# durtest4.net
KiCad netlist of a schematic drawn in EAGLE
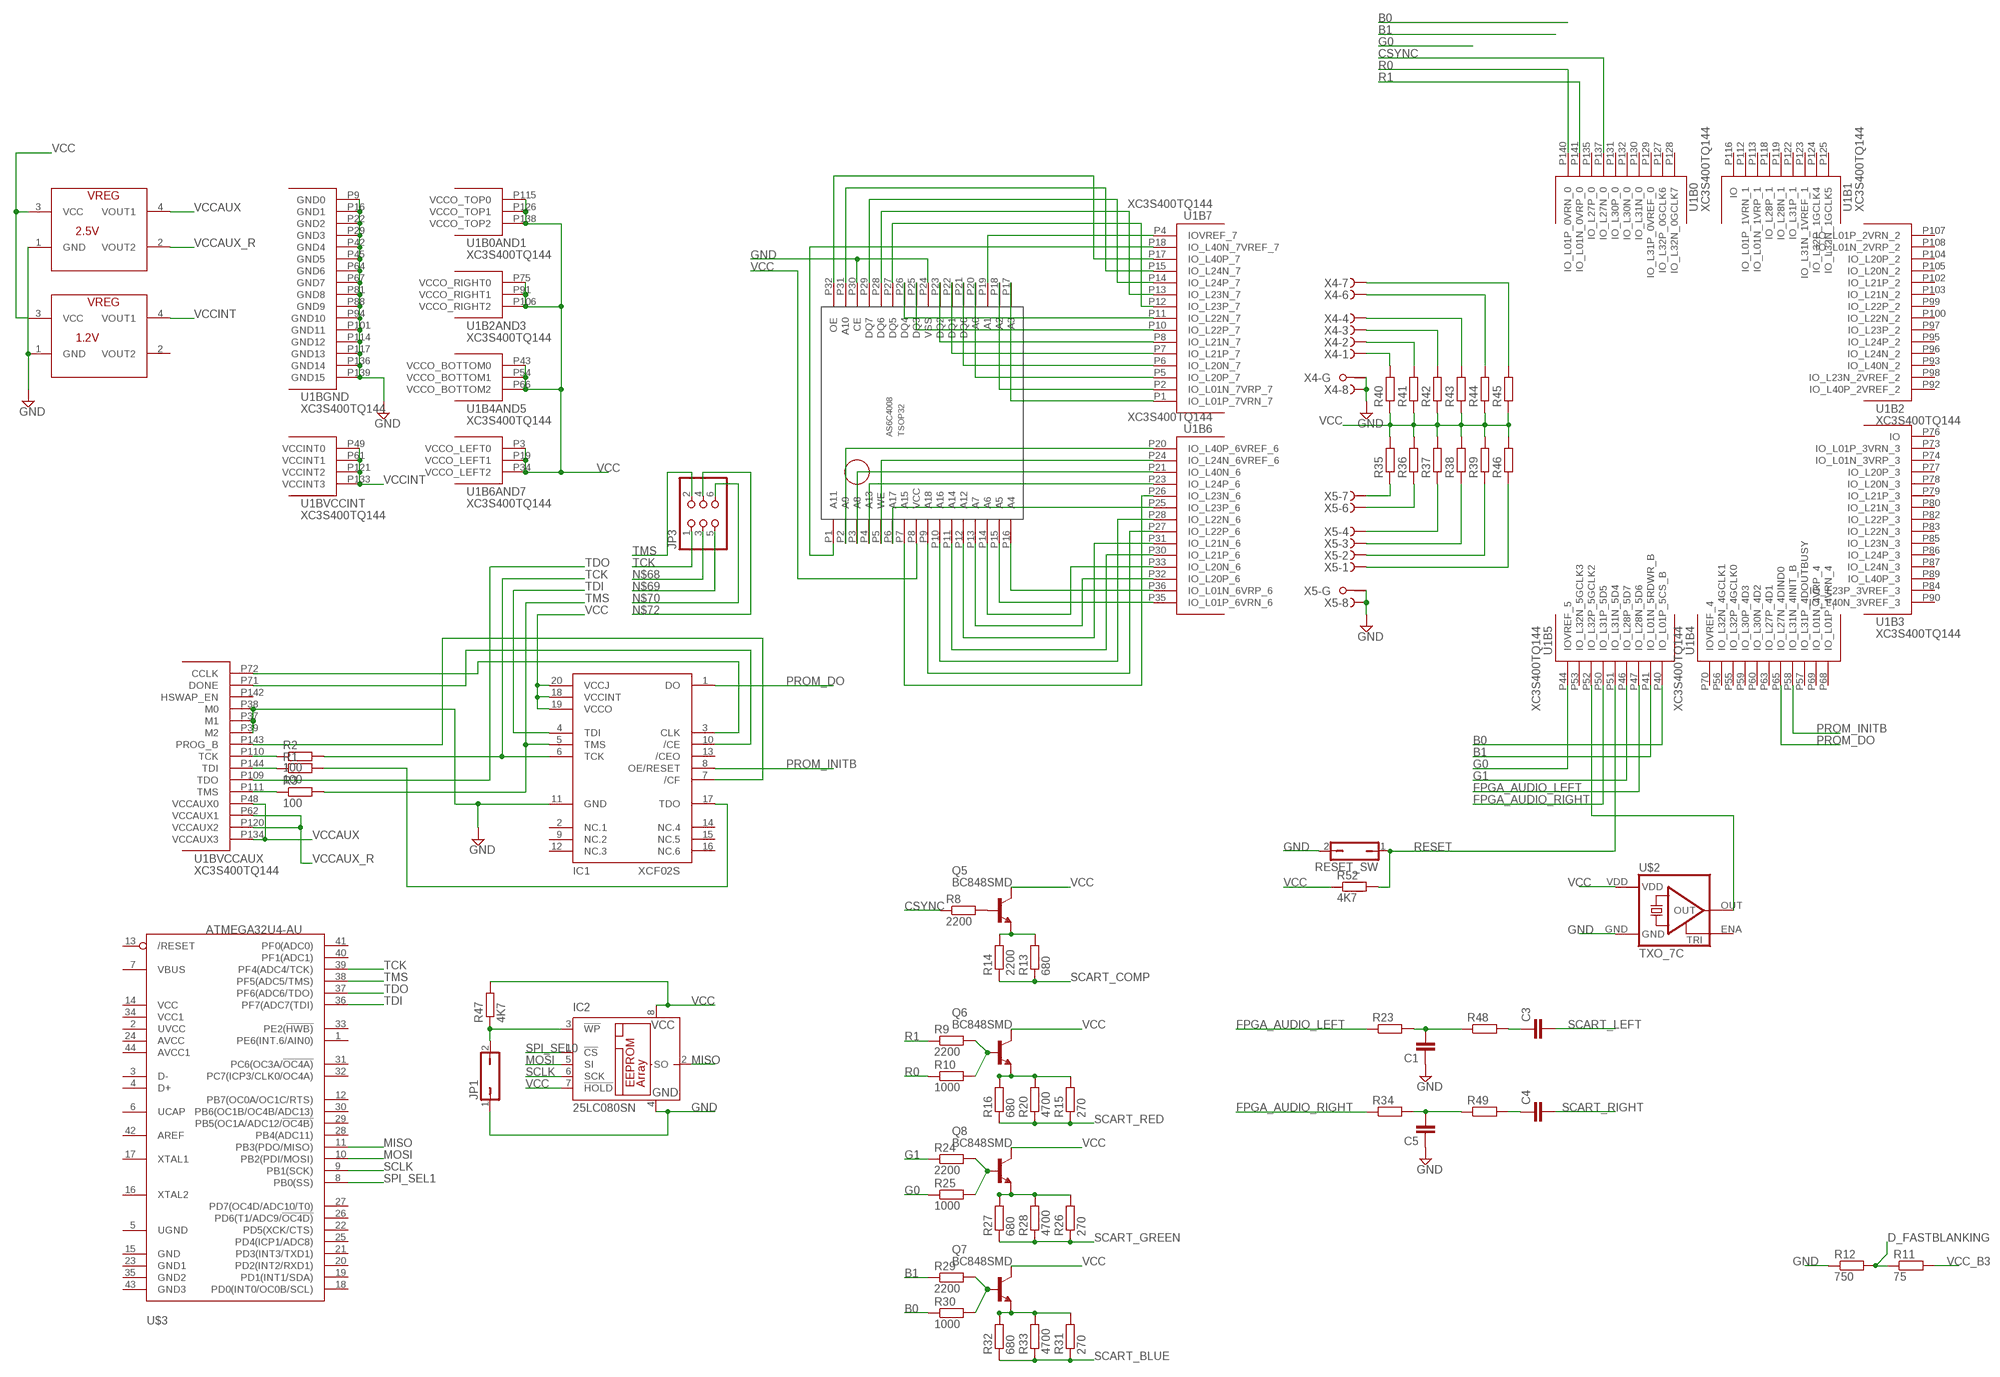
[diagram p0: schematic, sheet 1, part 1 of 2]
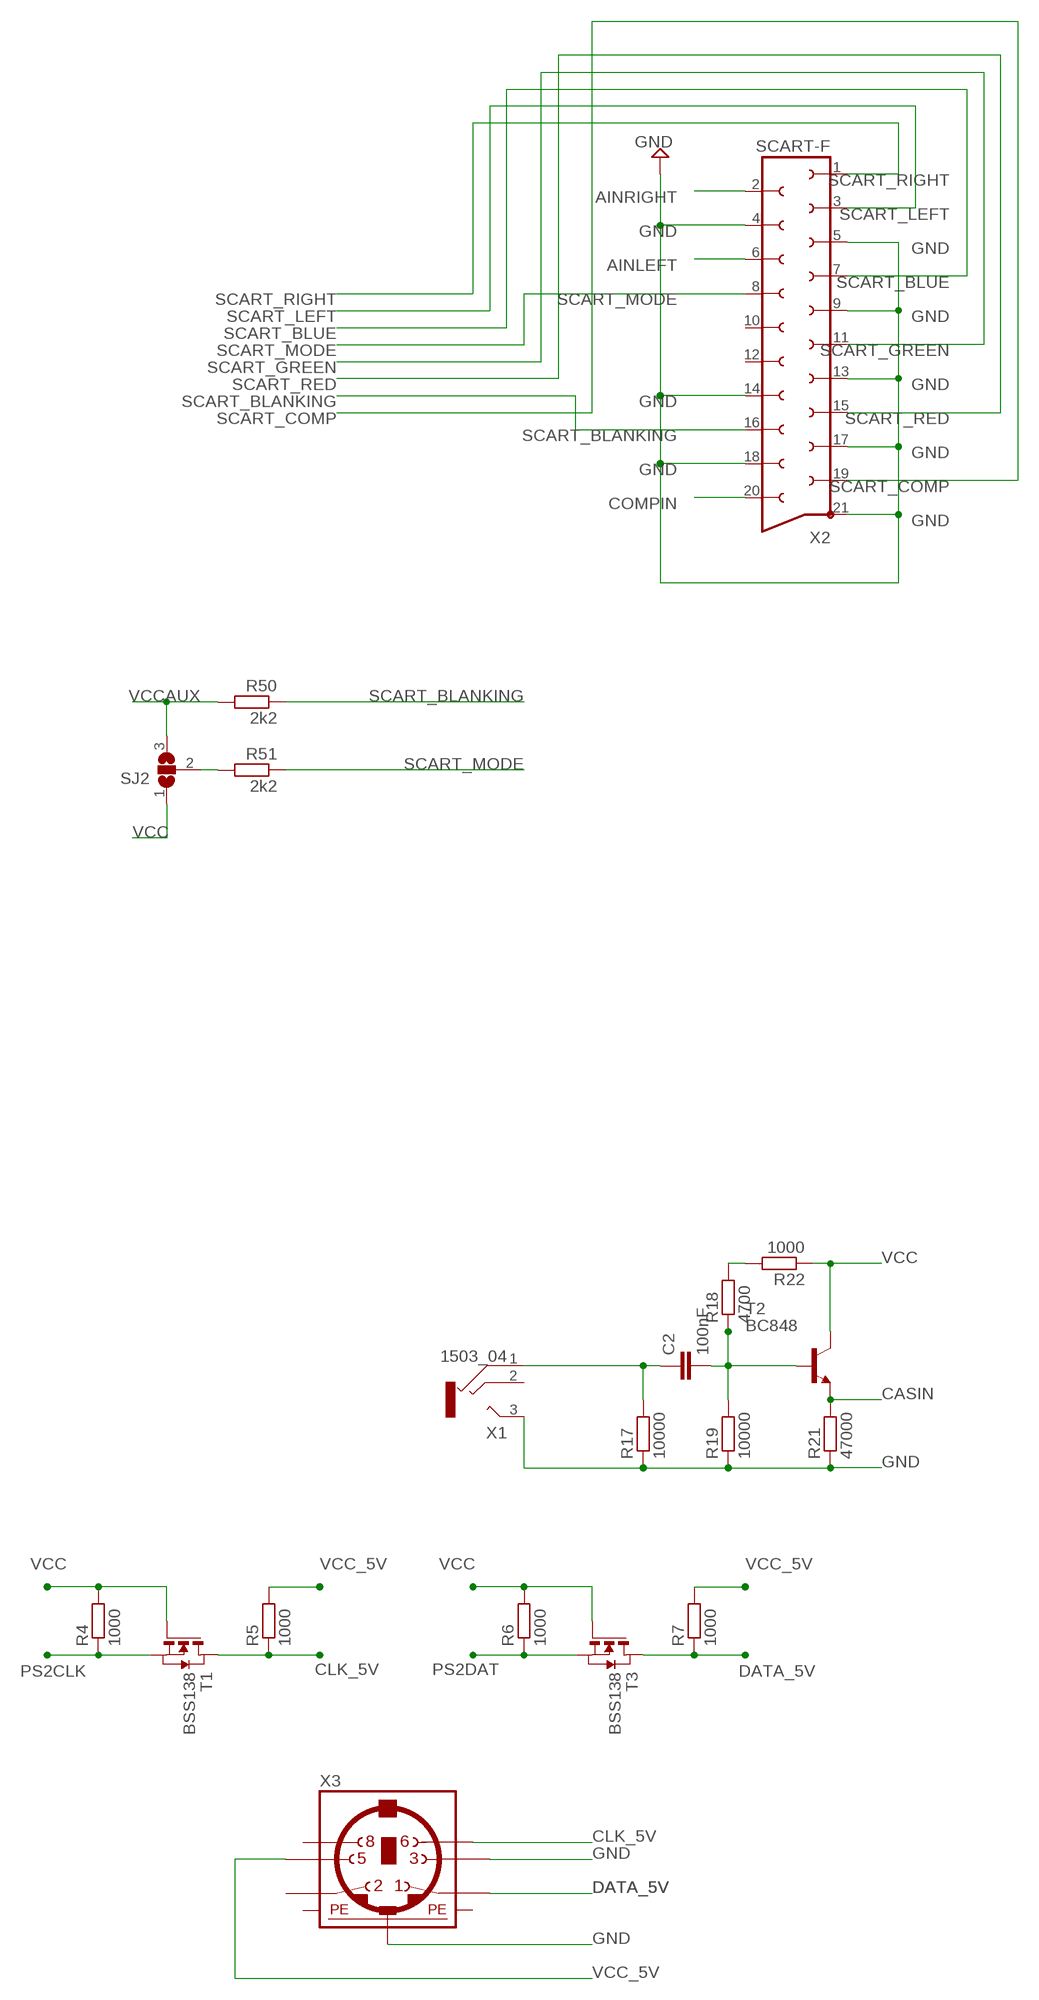
[diagram p1: schematic, sheet 1, part 2 of 2]

(export (version "E")
  (design (tool "Eeschema 10.0.6"))
  (components
    (comp (ref "C1")
      (value "C-EUC0603")
      (footprint "eagle-import:C0603")
      (libsource (lib "eagle-import") (part "C-EUC0603"))
    )
    (comp (ref "C2")
      (value "100nF")
      (footprint "eagle-import:C0603")
      (libsource (lib "eagle-import") (part "C-EUC0603"))
    )
    (comp (ref "C3")
      (value "C-EUC0603")
      (footprint "eagle-import:C0603")
      (libsource (lib "eagle-import") (part "C-EUC0603"))
    )
    (comp (ref "C4")
      (value "C-EUC0603")
      (footprint "eagle-import:C0603")
      (libsource (lib "eagle-import") (part "C-EUC0603"))
    )
    (comp (ref "C5")
      (value "C-EUC0603")
      (footprint "eagle-import:C0603")
      (libsource (lib "eagle-import") (part "C-EUC0603"))
    )
    (comp (ref "IC1")
      (value "XCF02S")
      (footprint "eagle-import:VO20")
      (libsource (lib "eagle-import") (part "XCF02S"))
    )
    (comp (ref "IC2")
      (value "25LC080SN")
      (footprint "eagle-import:SO-08")
      (fields (field (name "MF") "MICROCHIP") (field (name "MPN") "25LC080/SN"))
      (libsource (lib "eagle-import") (part "25SNLC080"))
    )
    (comp (ref "JP1")
      (value "JP1Q")
      (footprint "eagle-import:JP1")
      (libsource (lib "eagle-import") (part "JP1Q"))
    )
    (comp (ref "JP3")
      (value "PINHD-2X3")
      (footprint "eagle-import:2X03")
      (libsource (lib "eagle-import") (part "PINHD-2X3"))
    )
    (comp (ref "Q5")
      (value "BC848SMD")
      (footprint "eagle-import:SOT23")
      (libsource (lib "eagle-import") (part "BC848SMD"))
    )
    (comp (ref "Q6")
      (value "BC848SMD")
      (footprint "eagle-import:SOT23")
      (libsource (lib "eagle-import") (part "BC848SMD"))
    )
    (comp (ref "Q7")
      (value "BC848SMD")
      (footprint "eagle-import:SOT23")
      (libsource (lib "eagle-import") (part "BC848SMD"))
    )
    (comp (ref "Q8")
      (value "BC848SMD")
      (footprint "eagle-import:SOT23")
      (libsource (lib "eagle-import") (part "BC848SMD"))
    )
    (comp (ref "R1")
      (value "100")
      (footprint "eagle-import:R0805")
      (libsource (lib "eagle-import") (part "R-EU_R0805"))
    )
    (comp (ref "R2")
      (value "100")
      (footprint "eagle-import:R0805")
      (libsource (lib "eagle-import") (part "R-EU_R0805"))
    )
    (comp (ref "R3")
      (value "100")
      (footprint "eagle-import:R0805")
      (libsource (lib "eagle-import") (part "R-EU_R0805"))
    )
    (comp (ref "R4")
      (value "1000")
      (footprint "eagle-import:R0805")
      (libsource (lib "eagle-import") (part "R-EU_R0805"))
    )
    (comp (ref "R5")
      (value "1000")
      (footprint "eagle-import:R0805")
      (libsource (lib "eagle-import") (part "R-EU_R0805"))
    )
    (comp (ref "R6")
      (value "1000")
      (footprint "eagle-import:R0805")
      (libsource (lib "eagle-import") (part "R-EU_R0805"))
    )
    (comp (ref "R7")
      (value "1000")
      (footprint "eagle-import:R0805")
      (libsource (lib "eagle-import") (part "R-EU_R0805"))
    )
    (comp (ref "R8")
      (value "2200")
      (footprint "eagle-import:R0805")
      (libsource (lib "eagle-import") (part "R-EU_R0805"))
    )
    (comp (ref "R9")
      (value "2200")
      (footprint "eagle-import:R0805")
      (libsource (lib "eagle-import") (part "R-EU_R0805"))
    )
    (comp (ref "R10")
      (value "1000")
      (footprint "eagle-import:R0805")
      (libsource (lib "eagle-import") (part "R-EU_R0805"))
    )
    (comp (ref "R11")
      (value "75")
      (footprint "eagle-import:R0805")
      (libsource (lib "eagle-import") (part "R-EU_R0805"))
    )
    (comp (ref "R12")
      (value "750")
      (footprint "eagle-import:R0805")
      (libsource (lib "eagle-import") (part "R-EU_R0805"))
    )
    (comp (ref "R13")
      (value "680")
      (footprint "eagle-import:R0805")
      (libsource (lib "eagle-import") (part "R-EU_R0805"))
    )
    (comp (ref "R14")
      (value "2200")
      (footprint "eagle-import:R0805")
      (libsource (lib "eagle-import") (part "R-EU_R0805"))
    )
    (comp (ref "R15")
      (value "270")
      (footprint "eagle-import:R0805")
      (libsource (lib "eagle-import") (part "R-EU_R0805"))
    )
    (comp (ref "R16")
      (value "680")
      (footprint "eagle-import:R0805")
      (libsource (lib "eagle-import") (part "R-EU_R0805"))
    )
    (comp (ref "R17")
      (value "10000")
      (footprint "eagle-import:R0805")
      (libsource (lib "eagle-import") (part "R-EU_R0805"))
    )
    (comp (ref "R18")
      (value "4700")
      (footprint "eagle-import:R0805")
      (libsource (lib "eagle-import") (part "R-EU_R0805"))
    )
    (comp (ref "R19")
      (value "10000")
      (footprint "eagle-import:R0805")
      (libsource (lib "eagle-import") (part "R-EU_R0805"))
    )
    (comp (ref "R20")
      (value "4700")
      (footprint "eagle-import:R0805")
      (libsource (lib "eagle-import") (part "R-EU_R0805"))
    )
    (comp (ref "R21")
      (value "47000")
      (footprint "eagle-import:R0805")
      (libsource (lib "eagle-import") (part "R-EU_R0805"))
    )
    (comp (ref "R22")
      (value "1000")
      (footprint "eagle-import:R0805")
      (libsource (lib "eagle-import") (part "R-EU_R0805"))
    )
    (comp (ref "R23")
      (value "R-EU_M0805")
      (footprint "eagle-import:M0805")
      (libsource (lib "eagle-import") (part "resistor_R-EU_M0805"))
    )
    (comp (ref "R24")
      (value "2200")
      (footprint "eagle-import:R0805")
      (libsource (lib "eagle-import") (part "R-EU_R0805"))
    )
    (comp (ref "R25")
      (value "1000")
      (footprint "eagle-import:R0805")
      (libsource (lib "eagle-import") (part "R-EU_R0805"))
    )
    (comp (ref "R26")
      (value "270")
      (footprint "eagle-import:R0805")
      (libsource (lib "eagle-import") (part "R-EU_R0805"))
    )
    (comp (ref "R27")
      (value "680")
      (footprint "eagle-import:R0805")
      (libsource (lib "eagle-import") (part "R-EU_R0805"))
    )
    (comp (ref "R28")
      (value "4700")
      (footprint "eagle-import:R0805")
      (libsource (lib "eagle-import") (part "R-EU_R0805"))
    )
    (comp (ref "R29")
      (value "2200")
      (footprint "eagle-import:R0805")
      (libsource (lib "eagle-import") (part "R-EU_R0805"))
    )
    (comp (ref "R30")
      (value "1000")
      (footprint "eagle-import:R0805")
      (libsource (lib "eagle-import") (part "R-EU_R0805"))
    )
    (comp (ref "R31")
      (value "270")
      (footprint "eagle-import:R0805")
      (libsource (lib "eagle-import") (part "R-EU_R0805"))
    )
    (comp (ref "R32")
      (value "680")
      (footprint "eagle-import:R0805")
      (libsource (lib "eagle-import") (part "R-EU_R0805"))
    )
    (comp (ref "R33")
      (value "4700")
      (footprint "eagle-import:R0805")
      (libsource (lib "eagle-import") (part "R-EU_R0805"))
    )
    (comp (ref "R34")
      (value "R-EU_M0805")
      (footprint "eagle-import:M0805")
      (libsource (lib "eagle-import") (part "resistor_R-EU_M0805"))
    )
    (comp (ref "R35")
      (value "R-EU_M0805")
      (footprint "eagle-import:M0805")
      (libsource (lib "eagle-import") (part "resistor_R-EU_M0805"))
    )
    (comp (ref "R36")
      (value "R-EU_M0805")
      (footprint "eagle-import:M0805")
      (libsource (lib "eagle-import") (part "resistor_R-EU_M0805"))
    )
    (comp (ref "R37")
      (value "R-EU_M0805")
      (footprint "eagle-import:M0805")
      (libsource (lib "eagle-import") (part "resistor_R-EU_M0805"))
    )
    (comp (ref "R38")
      (value "R-EU_M0805")
      (footprint "eagle-import:M0805")
      (libsource (lib "eagle-import") (part "resistor_R-EU_M0805"))
    )
    (comp (ref "R39")
      (value "R-EU_M0805")
      (footprint "eagle-import:M0805")
      (libsource (lib "eagle-import") (part "resistor_R-EU_M0805"))
    )
    (comp (ref "R40")
      (value "R-EU_M0805")
      (footprint "eagle-import:M0805")
      (libsource (lib "eagle-import") (part "resistor_R-EU_M0805"))
    )
    (comp (ref "R41")
      (value "R-EU_M0805")
      (footprint "eagle-import:M0805")
      (libsource (lib "eagle-import") (part "resistor_R-EU_M0805"))
    )
    (comp (ref "R42")
      (value "R-EU_M0805")
      (footprint "eagle-import:M0805")
      (libsource (lib "eagle-import") (part "resistor_R-EU_M0805"))
    )
    (comp (ref "R43")
      (value "R-EU_M0805")
      (footprint "eagle-import:M0805")
      (libsource (lib "eagle-import") (part "resistor_R-EU_M0805"))
    )
    (comp (ref "R44")
      (value "R-EU_M0805")
      (footprint "eagle-import:M0805")
      (libsource (lib "eagle-import") (part "resistor_R-EU_M0805"))
    )
    (comp (ref "R45")
      (value "R-EU_M0805")
      (footprint "eagle-import:M0805")
      (libsource (lib "eagle-import") (part "resistor_R-EU_M0805"))
    )
    (comp (ref "R46")
      (value "R-EU_M0805")
      (footprint "eagle-import:M0805")
      (libsource (lib "eagle-import") (part "resistor_R-EU_M0805"))
    )
    (comp (ref "R47")
      (value "4K7")
      (footprint "eagle-import:R0805")
      (libsource (lib "eagle-import") (part "R-EU_R0805"))
    )
    (comp (ref "R48")
      (value "R-EU_M0805")
      (footprint "eagle-import:M0805")
      (libsource (lib "eagle-import") (part "resistor_R-EU_M0805"))
    )
    (comp (ref "R49")
      (value "R-EU_M0805")
      (footprint "eagle-import:M0805")
      (libsource (lib "eagle-import") (part "resistor_R-EU_M0805"))
    )
    (comp (ref "R50")
      (value "2k2")
      (footprint "eagle-import:M0805")
      (libsource (lib "eagle-import") (part "resistor_R-EU_M0805"))
    )
    (comp (ref "R51")
      (value "2k2")
      (footprint "eagle-import:M0805")
      (libsource (lib "eagle-import") (part "resistor_R-EU_M0805"))
    )
    (comp (ref "R52")
      (value "4K7")
      (footprint "eagle-import:M0805")
      (libsource (lib "eagle-import") (part "resistor_R-EU_M0805"))
    )
    (comp (ref "REG1.2")
      (value "1.2V")
      (footprint "eagle-import:SOT223")
      (libsource (lib "eagle-import") (part "NX1117"))
    )
    (comp (ref "REG2.5")
      (value "2.5V")
      (footprint "eagle-import:SOT223")
      (libsource (lib "eagle-import") (part "NX1117"))
    )
    (comp (ref "RESET_SW")
      (value "JP1Q")
      (footprint "eagle-import:JP1")
      (libsource (lib "eagle-import") (part "JP1Q"))
    )
    (comp (ref "SJ2")
      (value "SJ2W")
      (footprint "eagle-import:SJ_2")
      (libsource (lib "eagle-import") (part "SJ2W"))
    )
    (comp (ref "T1")
      (value "BSS138")
      (footprint "eagle-import:SOT-23")
      (libsource (lib "eagle-import") (part "NMOSSOT23"))
    )
    (comp (ref "T2")
      (value "BC848")
      (footprint "eagle-import:SOT23")
      (libsource (lib "eagle-import") (part "BC848"))
    )
    (comp (ref "T3")
      (value "BSS138")
      (footprint "eagle-import:SOT-23")
      (libsource (lib "eagle-import") (part "NMOSSOT23"))
    )
    (comp (ref "U$1")
      (value "AS6C4008")
      (footprint "eagle-import:TSOP32")
      (libsource (lib "eagle-import") (part "AS6C4008"))
    )
    (comp (ref "U$2")
      (value "TXO_7C")
      (footprint "eagle-import:OSC_7C")
      (libsource (lib "eagle-import") (part "TXO_7C"))
    )
    (comp (ref "U$3")
      (value "ATMEGA32U4-AU")
      (footprint "eagle-import:TQFP44")
      (libsource (lib "eagle-import") (part "ATMEGA32U4-AU"))
    )
    (comp (ref "U1")
      (value "XC3S400TQ144")
      (footprint "eagle-import:TQ144")
      (libsource (lib "eagle-import") (part "XC3S400TQ144"))
    )
    (comp (ref "X1")
      (value "1503_04")
      (footprint "eagle-import:1503_04")
      (libsource (lib "eagle-import") (part "1503_04"))
    )
    (comp (ref "X2")
      (value "SCART-F")
      (footprint "eagle-import:SCART-F")
      (libsource (lib "eagle-import") (part "SCART-F"))
    )
    (comp (ref "X3")
      (value "MINI_DIN_6")
      (footprint "eagle-import:M_DIN6")
      (libsource (lib "eagle-import") (part "MINI_DIN_6"))
    )
    (comp (ref "X4")
      (value "F09HPS")
      (footprint "eagle-import:F09HP")
      (libsource (lib "eagle-import") (part "F09HPS"))
    )
    (comp (ref "X5")
      (value "F09HPS")
      (footprint "eagle-import:F09HP")
      (libsource (lib "eagle-import") (part "F09HPS"))
    )
  )
  (nets
    (net (code "1") (name "/AINLEFT") (class "Default")
      (node (ref "X2") (pin "6") (pinfunction "6_6") (pintype "passive"))
    )
    (net (code "2") (name "/AINRIGHT") (class "Default")
      (node (ref "X2") (pin "2") (pinfunction "2_2") (pintype "passive"))
    )
    (net (code "3") (name "/B0") (class "Default")
      (node (ref "R30") (pin "1") (pinfunction "1_1") (pintype "passive"))
      (node (ref "U1") (pin "P40") (pinfunction "IO_L01P_5CS_B_P40") (pintype "bidirectional"))
    )
    (net (code "4") (name "/B1") (class "Default")
      (node (ref "R29") (pin "1") (pinfunction "1_1") (pintype "passive"))
      (node (ref "U1") (pin "P41") (pinfunction "IO_L01N_5RDWR_B_P41") (pintype "bidirectional"))
    )
    (net (code "5") (name "/CASIN") (class "Default")
      (node (ref "R21") (pin "2") (pinfunction "2_2") (pintype "passive"))
      (node (ref "T2") (pin "2") (pinfunction "E_2") (pintype "passive"))
    )
    (net (code "6") (name "/CLK_5V") (class "Default")
      (node (ref "R5") (pin "1") (pinfunction "1_1") (pintype "passive"))
      (node (ref "T1") (pin "1") (pinfunction "D_1") (pintype "passive"))
      (node (ref "X3") (pin "6") (pinfunction "6_6") (pintype "passive"))
    )
    (net (code "7") (name "/COMPIN") (class "Default")
      (node (ref "X2") (pin "20") (pinfunction "20_20") (pintype "passive"))
    )
    (net (code "8") (name "/CSYNC") (class "Default")
      (node (ref "R8") (pin "1") (pinfunction "1_1") (pintype "passive"))
      (node (ref "U1") (pin "P137") (pinfunction "IO_L27N_0_P137") (pintype "bidirectional"))
    )
    (net (code "9") (name "/DATA_5V") (class "Default")
      (node (ref "R7") (pin "1") (pinfunction "1_1") (pintype "passive"))
      (node (ref "T3") (pin "1") (pinfunction "D_1") (pintype "passive"))
      (node (ref "X3") (pin "1") (pinfunction "1_1") (pintype "passive"))
    )
    (net (code "10") (name "/D_FASTBLANKING") (class "Default")
      (node (ref "R11") (pin "1") (pinfunction "1_1") (pintype "passive"))
      (node (ref "R12") (pin "2") (pinfunction "2_2") (pintype "passive"))
    )
    (net (code "11") (name "/FPGA_AUDIO_LEFT") (class "Default")
      (node (ref "R23") (pin "1") (pinfunction "1_1") (pintype "passive"))
      (node (ref "U1") (pin "P47") (pinfunction "IO_L28N_5D6_P47") (pintype "bidirectional"))
    )
    (net (code "12") (name "/FPGA_AUDIO_RIGHT") (class "Default")
      (node (ref "R34") (pin "1") (pinfunction "1_1") (pintype "passive"))
      (node (ref "U1") (pin "P50") (pinfunction "IO_L31P_5D5_P50") (pintype "bidirectional"))
    )
    (net (code "13") (name "/G0") (class "Default")
      (node (ref "R25") (pin "1") (pinfunction "1_1") (pintype "passive"))
      (node (ref "U1") (pin "P44") (pinfunction "IOVREF_5_P44") (pintype "bidirectional"))
    )
    (net (code "14") (name "/G1") (class "Default")
      (node (ref "R24") (pin "1") (pinfunction "1_1") (pintype "passive"))
      (node (ref "U1") (pin "P46") (pinfunction "IO_L28P_5D7_P46") (pintype "bidirectional"))
    )
    (net (code "15") (name "/MISO") (class "Default")
      (node (ref "IC2") (pin "2") (pinfunction "SO_2") (pintype "bidirectional"))
      (node (ref "U$3") (pin "11") (pinfunction "PB3(PDO/MISO)_11") (pintype "bidirectional"))
    )
    (net (code "16") (name "/MOSI") (class "Default")
      (node (ref "IC2") (pin "5") (pinfunction "SI_5") (pintype "input"))
      (node (ref "U$3") (pin "10") (pinfunction "PB2(PDI/MOSI)_10") (pintype "bidirectional"))
    )
    (net (code "17") (name "/N$68") (class "Default")
      (node (ref "JP3") (pin "3") (pinfunction "3_3") (pintype "passive"))
    )
    (net (code "18") (name "/N$69") (class "Default")
      (node (ref "JP3") (pin "5") (pinfunction "5_5") (pintype "passive"))
    )
    (net (code "19") (name "/N$70") (class "Default")
      (node (ref "JP3") (pin "6") (pinfunction "6_6") (pintype "passive"))
    )
    (net (code "20") (name "/N$72") (class "Default")
      (node (ref "JP3") (pin "4") (pinfunction "4_4") (pintype "passive"))
    )
    (net (code "21") (name "/PE1") (class "Default")
      (node (ref "X3") (pin "SH1") (pinfunction "PE1_SH1") (pintype "power_in"))
    )
    (net (code "22") (name "/PE3") (class "Default")
      (node (ref "X3") (pin "SH3") (pinfunction "PE3_SH3") (pintype "power_in"))
    )
    (net (code "23") (name "/PROM_DO") (class "Default")
      (node (ref "IC1") (pin "1") (pinfunction "DO_1") (pintype "bidirectional"))
      (node (ref "U1") (pin "P65") (pinfunction "IO_L27N_4DIND0_P65") (pintype "bidirectional"))
    )
    (net (code "24") (name "/PROM_INITB") (class "Default")
      (node (ref "IC1") (pin "8") (pinfunction "OE/RESET_8") (pintype "bidirectional"))
      (node (ref "U1") (pin "P58") (pinfunction "IO_L31N_4INIT_B_P58") (pintype "bidirectional"))
    )
    (net (code "25") (name "/PS2CLK") (class "Default")
      (node (ref "R4") (pin "1") (pinfunction "1_1") (pintype "passive"))
      (node (ref "T1") (pin "2") (pinfunction "S_2") (pintype "passive"))
    )
    (net (code "26") (name "/PS2DAT") (class "Default")
      (node (ref "R6") (pin "1") (pinfunction "1_1") (pintype "passive"))
      (node (ref "T3") (pin "2") (pinfunction "S_2") (pintype "passive"))
    )
    (net (code "27") (name "/R0") (class "Default")
      (node (ref "R10") (pin "1") (pinfunction "1_1") (pintype "passive"))
      (node (ref "U1") (pin "P140") (pinfunction "IO_L01P_0VRN_0_P140") (pintype "bidirectional"))
    )
    (net (code "28") (name "/R1") (class "Default")
      (node (ref "R9") (pin "1") (pinfunction "1_1") (pintype "passive"))
      (node (ref "U1") (pin "P141") (pinfunction "IO_L01N_0VRP_0_P141") (pintype "bidirectional"))
    )
    (net (code "29") (name "/RESET") (class "Default")
      (node (ref "R52") (pin "2") (pinfunction "2_2") (pintype "passive"))
      (node (ref "RESET_SW") (pin "1") (pinfunction "1_1") (pintype "passive"))
      (node (ref "U1") (pin "P51") (pinfunction "IO_L31N_5D4_P51") (pintype "bidirectional"))
    )
    (net (code "30") (name "/SCART_BLANKING") (class "Default")
      (node (ref "R50") (pin "1") (pinfunction "1_1") (pintype "passive"))
      (node (ref "X2") (pin "16") (pinfunction "16_16") (pintype "passive"))
    )
    (net (code "31") (name "/SCART_BLUE") (class "Default")
      (node (ref "R31") (pin "1") (pinfunction "1_1") (pintype "passive"))
      (node (ref "R32") (pin "1") (pinfunction "1_1") (pintype "passive"))
      (node (ref "R33") (pin "1") (pinfunction "1_1") (pintype "passive"))
      (node (ref "X2") (pin "7") (pinfunction "7_7") (pintype "passive"))
    )
    (net (code "32") (name "/SCART_COMP") (class "Default")
      (node (ref "R13") (pin "1") (pinfunction "1_1") (pintype "passive"))
      (node (ref "R14") (pin "1") (pinfunction "1_1") (pintype "passive"))
      (node (ref "X2") (pin "19") (pinfunction "19_19") (pintype "passive"))
    )
    (net (code "33") (name "/SCART_GREEN") (class "Default")
      (node (ref "R26") (pin "1") (pinfunction "1_1") (pintype "passive"))
      (node (ref "R27") (pin "1") (pinfunction "1_1") (pintype "passive"))
      (node (ref "R28") (pin "1") (pinfunction "1_1") (pintype "passive"))
      (node (ref "X2") (pin "11") (pinfunction "11_11") (pintype "passive"))
    )
    (net (code "34") (name "/SCART_LEFT") (class "Default")
      (node (ref "C3") (pin "2") (pinfunction "2_2") (pintype "passive"))
      (node (ref "X2") (pin "3") (pinfunction "3_3") (pintype "passive"))
    )
    (net (code "35") (name "/SCART_MODE") (class "Default")
      (node (ref "R51") (pin "1") (pinfunction "1_1") (pintype "passive"))
      (node (ref "X2") (pin "8") (pinfunction "8_8") (pintype "passive"))
    )
    (net (code "36") (name "/SCART_RED") (class "Default")
      (node (ref "R15") (pin "1") (pinfunction "1_1") (pintype "passive"))
      (node (ref "R16") (pin "1") (pinfunction "1_1") (pintype "passive"))
      (node (ref "R20") (pin "1") (pinfunction "1_1") (pintype "passive"))
      (node (ref "X2") (pin "15") (pinfunction "15_15") (pintype "passive"))
    )
    (net (code "37") (name "/SCART_RIGHT") (class "Default")
      (node (ref "C4") (pin "2") (pinfunction "2_2") (pintype "passive"))
      (node (ref "X2") (pin "1") (pinfunction "1_1") (pintype "passive"))
    )
    (net (code "38") (name "/SCLK") (class "Default")
      (node (ref "IC2") (pin "6") (pinfunction "SCK_6") (pintype "input"))
      (node (ref "U$3") (pin "9") (pinfunction "PB1(SCK)_9") (pintype "bidirectional"))
    )
    (net (code "39") (name "/SPI_SEL0") (class "Default")
      (node (ref "IC2") (pin "1") (pinfunction "~{CS}_1") (pintype "input"))
    )
    (net (code "40") (name "/SPI_SEL1") (class "Default")
      (node (ref "U$3") (pin "8") (pinfunction "PB0(SS)_8") (pintype "bidirectional"))
    )
    (net (code "41") (name "/TCK") (class "Default")
      (node (ref "IC1") (pin "6") (pinfunction "TCK_6") (pintype "bidirectional"))
      (node (ref "JP3") (pin "1") (pinfunction "1_1") (pintype "passive"))
      (node (ref "R2") (pin "2") (pinfunction "2_2") (pintype "passive"))
      (node (ref "U$3") (pin "39") (pinfunction "PF4(ADC4/TCK)_39") (pintype "bidirectional"))
    )
    (net (code "42") (name "/TDI") (class "Default")
      (node (ref "IC1") (pin "4") (pinfunction "TDI_4") (pintype "bidirectional"))
      (node (ref "U$3") (pin "36") (pinfunction "PF7(ADC7(TDI)_36") (pintype "bidirectional"))
    )
    (net (code "43") (name "/TDO") (class "Default")
      (node (ref "U$3") (pin "37") (pinfunction "PF6(ADC6/TDO)_37") (pintype "bidirectional"))
      (node (ref "U1") (pin "P109") (pinfunction "TDO_P109") (pintype "bidirectional"))
    )
    (net (code "44") (name "/TMS") (class "Default")
      (node (ref "IC1") (pin "5") (pinfunction "TMS_5") (pintype "bidirectional"))
      (node (ref "JP3") (pin "2") (pinfunction "2_2") (pintype "passive"))
      (node (ref "R3") (pin "2") (pinfunction "2_2") (pintype "passive"))
      (node (ref "U$3") (pin "38") (pinfunction "PF5(ADC5/TMS)_38") (pintype "bidirectional"))
    )
    (net (code "45") (name "/VCC") (class "Default")
      (node (ref "IC1") (pin "18") (pinfunction "VCCINT_18") (pintype "bidirectional"))
      (node (ref "IC1") (pin "19") (pinfunction "VCCO_19") (pintype "bidirectional"))
      (node (ref "IC1") (pin "20") (pinfunction "VCCJ_20") (pintype "bidirectional"))
      (node (ref "IC2") (pin "7") (pinfunction "~{HOLD}_7") (pintype "input"))
      (node (ref "IC2") (pin "8") (pinfunction "VCC_8") (pintype "power_in"))
      (node (ref "Q5") (pin "3") (pinfunction "C_3") (pintype "passive"))
      (node (ref "Q6") (pin "3") (pinfunction "C_3") (pintype "passive"))
      (node (ref "Q7") (pin "3") (pinfunction "C_3") (pintype "passive"))
      (node (ref "Q8") (pin "3") (pinfunction "C_3") (pintype "passive"))
      (node (ref "R22") (pin "1") (pinfunction "1_1") (pintype "passive"))
      (node (ref "R35") (pin "2") (pinfunction "2_2") (pintype "passive"))
      (node (ref "R36") (pin "2") (pinfunction "2_2") (pintype "passive"))
      (node (ref "R37") (pin "2") (pinfunction "2_2") (pintype "passive"))
      (node (ref "R38") (pin "2") (pinfunction "2_2") (pintype "passive"))
      (node (ref "R39") (pin "2") (pinfunction "2_2") (pintype "passive"))
      (node (ref "R4") (pin "2") (pinfunction "2_2") (pintype "passive"))
      (node (ref "R40") (pin "1") (pinfunction "1_1") (pintype "passive"))
      (node (ref "R41") (pin "1") (pinfunction "1_1") (pintype "passive"))
      (node (ref "R42") (pin "1") (pinfunction "1_1") (pintype "passive"))
      (node (ref "R43") (pin "1") (pinfunction "1_1") (pintype "passive"))
      (node (ref "R44") (pin "1") (pinfunction "1_1") (pintype "passive"))
      (node (ref "R45") (pin "1") (pinfunction "1_1") (pintype "passive"))
      (node (ref "R46") (pin "2") (pinfunction "2_2") (pintype "passive"))
      (node (ref "R47") (pin "2") (pinfunction "2_2") (pintype "passive"))
      (node (ref "R52") (pin "1") (pinfunction "1_1") (pintype "passive"))
      (node (ref "R6") (pin "2") (pinfunction "2_2") (pintype "passive"))
      (node (ref "REG1.2") (pin "3") (pinfunction "VCC_3") (pintype "bidirectional"))
      (node (ref "REG2.5") (pin "3") (pinfunction "VCC_3") (pintype "bidirectional"))
      (node (ref "SJ2") (pin "1") (pinfunction "1_1") (pintype "passive"))
      (node (ref "T1") (pin "3") (pinfunction "G_3") (pintype "passive"))
      (node (ref "T2") (pin "3") (pinfunction "C_3") (pintype "passive"))
      (node (ref "T3") (pin "3") (pinfunction "G_3") (pintype "passive"))
      (node (ref "U$1") (pin "P8") (pinfunction "VCC_P8") (pintype "bidirectional"))
      (node (ref "U$2") (pin "VDD") (pinfunction "VDD_VDD") (pintype "power_in"))
      (node (ref "U1") (pin "P106") (pinfunction "VCCO_RIGHT2_P106") (pintype "passive"))
      (node (ref "U1") (pin "P115") (pinfunction "VCCO_TOP0_P115") (pintype "passive"))
      (node (ref "U1") (pin "P126") (pinfunction "VCCO_TOP1_P126") (pintype "passive"))
      (node (ref "U1") (pin "P138") (pinfunction "VCCO_TOP2_P138") (pintype "passive"))
      (node (ref "U1") (pin "P19") (pinfunction "VCCO_LEFT1_P19") (pintype "passive"))
      (node (ref "U1") (pin "P3") (pinfunction "VCCO_LEFT0_P3") (pintype "passive"))
      (node (ref "U1") (pin "P34") (pinfunction "VCCO_LEFT2_P34") (pintype "passive"))
      (node (ref "U1") (pin "P43") (pinfunction "VCCO_BOTTOM0_P43") (pintype "passive"))
      (node (ref "U1") (pin "P54") (pinfunction "VCCO_BOTTOM1_P54") (pintype "passive"))
      (node (ref "U1") (pin "P66") (pinfunction "VCCO_BOTTOM2_P66") (pintype "passive"))
      (node (ref "U1") (pin "P75") (pinfunction "VCCO_RIGHT0_P75") (pintype "passive"))
      (node (ref "U1") (pin "P91") (pinfunction "VCCO_RIGHT1_P91") (pintype "passive"))
    )
    (net (code "46") (name "/VCCAUX") (class "Default")
      (node (ref "R50") (pin "2") (pinfunction "2_2") (pintype "passive"))
      (node (ref "REG2.5") (pin "4") (pinfunction "VOUT1_4") (pintype "bidirectional"))
      (node (ref "SJ2") (pin "3") (pinfunction "3_3") (pintype "passive"))
      (node (ref "U1") (pin "P134") (pinfunction "VCCAUX3_P134") (pintype "passive"))
      (node (ref "U1") (pin "P48") (pinfunction "VCCAUX0_P48") (pintype "passive"))
    )
    (net (code "47") (name "/VCCAUX_R") (class "Default")
      (node (ref "REG2.5") (pin "2") (pinfunction "VOUT2_2") (pintype "bidirectional"))
      (node (ref "U1") (pin "P120") (pinfunction "VCCAUX2_P120") (pintype "passive"))
      (node (ref "U1") (pin "P62") (pinfunction "VCCAUX1_P62") (pintype "passive"))
    )
    (net (code "48") (name "/VCCINT") (class "Default")
      (node (ref "REG1.2") (pin "4") (pinfunction "VOUT1_4") (pintype "bidirectional"))
      (node (ref "U1") (pin "P121") (pinfunction "VCCINT2_P121") (pintype "passive"))
      (node (ref "U1") (pin "P133") (pinfunction "VCCINT3_P133") (pintype "passive"))
      (node (ref "U1") (pin "P49") (pinfunction "VCCINT0_P49") (pintype "passive"))
      (node (ref "U1") (pin "P61") (pinfunction "VCCINT1_P61") (pintype "passive"))
    )
    (net (code "49") (name "/VCC_5V") (class "Default")
      (node (ref "R5") (pin "2") (pinfunction "2_2") (pintype "passive"))
      (node (ref "R7") (pin "2") (pinfunction "2_2") (pintype "passive"))
      (node (ref "X3") (pin "5") (pinfunction "5_5") (pintype "passive"))
    )
    (net (code "50") (name "/VCC_B3") (class "Default")
      (node (ref "R11") (pin "2") (pinfunction "2_2") (pintype "passive"))
    )
    (net (code "51") (name "GND") (class "Default")
      (node (ref "C1") (pin "1") (pinfunction "1_1") (pintype "passive"))
      (node (ref "C5") (pin "1") (pinfunction "1_1") (pintype "passive"))
      (node (ref "IC1") (pin "11") (pinfunction "GND_11") (pintype "bidirectional"))
      (node (ref "IC2") (pin "4") (pinfunction "GND_4") (pintype "power_in"))
      (node (ref "JP1") (pin "1") (pinfunction "1_1") (pintype "passive"))
      (node (ref "R12") (pin "1") (pinfunction "1_1") (pintype "passive"))
      (node (ref "R17") (pin "1") (pinfunction "1_1") (pintype "passive"))
      (node (ref "R19") (pin "1") (pinfunction "1_1") (pintype "passive"))
      (node (ref "R21") (pin "1") (pinfunction "1_1") (pintype "passive"))
      (node (ref "REG1.2") (pin "1") (pinfunction "GND_1") (pintype "bidirectional"))
      (node (ref "REG2.5") (pin "1") (pinfunction "GND_1") (pintype "bidirectional"))
      (node (ref "RESET_SW") (pin "2") (pinfunction "2_2") (pintype "passive"))
      (node (ref "U$1") (pin "P24") (pinfunction "VSS_P24") (pintype "bidirectional"))
      (node (ref "U$1") (pin "P30") (pinfunction "CE_P30") (pintype "bidirectional"))
      (node (ref "U$2") (pin "GND") (pinfunction "GND_GND") (pintype "power_in"))
      (node (ref "U1") (pin "P101") (pinfunction "GND11_P101") (pintype "passive"))
      (node (ref "U1") (pin "P114") (pinfunction "GND12_P114") (pintype "passive"))
      (node (ref "U1") (pin "P117") (pinfunction "GND13_P117") (pintype "passive"))
      (node (ref "U1") (pin "P136") (pinfunction "GND14_P136") (pintype "passive"))
      (node (ref "U1") (pin "P139") (pinfunction "GND15_P139") (pintype "passive"))
      (node (ref "U1") (pin "P16") (pinfunction "GND1_P16") (pintype "passive"))
      (node (ref "U1") (pin "P22") (pinfunction "GND2_P22") (pintype "passive"))
      (node (ref "U1") (pin "P29") (pinfunction "GND3_P29") (pintype "passive"))
      (node (ref "U1") (pin "P37") (pinfunction "M1_P37") (pintype "bidirectional"))
      (node (ref "U1") (pin "P38") (pinfunction "M0_P38") (pintype "bidirectional"))
      (node (ref "U1") (pin "P39") (pinfunction "M2_P39") (pintype "bidirectional"))
      (node (ref "U1") (pin "P42") (pinfunction "GND4_P42") (pintype "passive"))
      (node (ref "U1") (pin "P45") (pinfunction "GND5_P45") (pintype "passive"))
      (node (ref "U1") (pin "P64") (pinfunction "GND6_P64") (pintype "passive"))
      (node (ref "U1") (pin "P67") (pinfunction "GND7_P67") (pintype "passive"))
      (node (ref "U1") (pin "P81") (pinfunction "GND8_P81") (pintype "passive"))
      (node (ref "U1") (pin "P88") (pinfunction "GND9_P88") (pintype "passive"))
      (node (ref "U1") (pin "P9") (pinfunction "GND0_P9") (pintype "passive"))
      (node (ref "U1") (pin "P94") (pinfunction "GND10_P94") (pintype "passive"))
      (node (ref "X1") (pin "3") (pinfunction "2_3") (pintype "passive"))
      (node (ref "X2") (pin "13") (pinfunction "13_13") (pintype "passive"))
      (node (ref "X2") (pin "14") (pinfunction "14_14") (pintype "passive"))
      (node (ref "X2") (pin "17") (pinfunction "17_17") (pintype "passive"))
      (node (ref "X2") (pin "18") (pinfunction "18_18") (pintype "passive"))
      (node (ref "X2") (pin "21") (pinfunction "21_21") (pintype "passive"))
      (node (ref "X2") (pin "4") (pinfunction "4_4") (pintype "passive"))
      (node (ref "X2") (pin "5") (pinfunction "5_5") (pintype "passive"))
      (node (ref "X2") (pin "9") (pinfunction "9_9") (pintype "passive"))
      (node (ref "X3") (pin "3") (pinfunction "3_3") (pintype "passive"))
      (node (ref "X3") (pin "SH2") (pinfunction "PE2_SH2") (pintype "power_in"))
      (node (ref "X4") (pin "8") (pinfunction "F_8") (pintype "passive"))
      (node (ref "X4") (pin "G1") (pinfunction "G1_G1") (pintype "passive"))
      (node (ref "X5") (pin "8") (pinfunction "F_8") (pintype "passive"))
      (node (ref "X5") (pin "G1") (pinfunction "G1_G1") (pintype "passive"))
    )
    (net (code "52") (name "Net-(C1-Pad2)") (class "Default")
      (node (ref "C1") (pin "2") (pinfunction "2_2") (pintype "passive"))
      (node (ref "R23") (pin "2") (pinfunction "2_2") (pintype "passive"))
      (node (ref "R48") (pin "1") (pinfunction "1_1") (pintype "passive"))
    )
    (net (code "53") (name "Net-(C2-Pad1)") (class "Default")
      (node (ref "C2") (pin "1") (pinfunction "1_1") (pintype "passive"))
      (node (ref "R17") (pin "2") (pinfunction "2_2") (pintype "passive"))
      (node (ref "X1") (pin "1") (pinfunction "1_1") (pintype "passive"))
    )
    (net (code "54") (name "Net-(C3-Pad1)") (class "Default")
      (node (ref "C3") (pin "1") (pinfunction "1_1") (pintype "passive"))
      (node (ref "R48") (pin "2") (pinfunction "2_2") (pintype "passive"))
    )
    (net (code "55") (name "Net-(C4-Pad1)") (class "Default")
      (node (ref "C4") (pin "1") (pinfunction "1_1") (pintype "passive"))
      (node (ref "R49") (pin "2") (pinfunction "2_2") (pintype "passive"))
    )
    (net (code "56") (name "Net-(C5-Pad2)") (class "Default")
      (node (ref "C5") (pin "2") (pinfunction "2_2") (pintype "passive"))
      (node (ref "R34") (pin "2") (pinfunction "2_2") (pintype "passive"))
      (node (ref "R49") (pin "1") (pinfunction "1_1") (pintype "passive"))
    )
    (net (code "57") (name "Net-(IC1-CLK)") (class "Default")
      (node (ref "IC1") (pin "3") (pinfunction "CLK_3") (pintype "bidirectional"))
      (node (ref "U1") (pin "P72") (pinfunction "CCLK_P72") (pintype "bidirectional"))
    )
    (net (code "58") (name "Net-(IC1-TDO)") (class "Default")
      (node (ref "IC1") (pin "17") (pinfunction "TDO_17") (pintype "bidirectional"))
      (node (ref "R1") (pin "2") (pinfunction "2_2") (pintype "passive"))
    )
    (net (code "59") (name "Net-(IC1-{slash}CE)") (class "Default")
      (node (ref "IC1") (pin "10") (pinfunction "/CE_10") (pintype "bidirectional"))
      (node (ref "U1") (pin "P71") (pinfunction "DONE_P71") (pintype "bidirectional"))
    )
    (net (code "60") (name "Net-(IC1-{slash}CF)") (class "Default")
      (node (ref "IC1") (pin "7") (pinfunction "/CF_7") (pintype "bidirectional"))
      (node (ref "U1") (pin "P143") (pinfunction "PROG_B_P143") (pintype "bidirectional"))
    )
    (net (code "61") (name "Net-(IC2-~{WP})") (class "Default")
      (node (ref "IC2") (pin "3") (pinfunction "~{WP}_3") (pintype "input"))
      (node (ref "JP1") (pin "2") (pinfunction "2_2") (pintype "passive"))
      (node (ref "R47") (pin "1") (pinfunction "1_1") (pintype "passive"))
    )
    (net (code "62") (name "Net-(Q5-B)") (class "Default")
      (node (ref "Q5") (pin "1") (pinfunction "B_1") (pintype "passive"))
      (node (ref "R8") (pin "2") (pinfunction "2_2") (pintype "passive"))
    )
    (net (code "63") (name "Net-(Q5-E)") (class "Default")
      (node (ref "Q5") (pin "2") (pinfunction "E_2") (pintype "passive"))
      (node (ref "R13") (pin "2") (pinfunction "2_2") (pintype "passive"))
      (node (ref "R14") (pin "2") (pinfunction "2_2") (pintype "passive"))
    )
    (net (code "64") (name "Net-(Q6-B)") (class "Default")
      (node (ref "Q6") (pin "1") (pinfunction "B_1") (pintype "passive"))
      (node (ref "R10") (pin "2") (pinfunction "2_2") (pintype "passive"))
      (node (ref "R9") (pin "2") (pinfunction "2_2") (pintype "passive"))
    )
    (net (code "65") (name "Net-(Q6-E)") (class "Default")
      (node (ref "Q6") (pin "2") (pinfunction "E_2") (pintype "passive"))
      (node (ref "R15") (pin "2") (pinfunction "2_2") (pintype "passive"))
      (node (ref "R16") (pin "2") (pinfunction "2_2") (pintype "passive"))
      (node (ref "R20") (pin "2") (pinfunction "2_2") (pintype "passive"))
    )
    (net (code "66") (name "Net-(Q7-B)") (class "Default")
      (node (ref "Q7") (pin "1") (pinfunction "B_1") (pintype "passive"))
      (node (ref "R29") (pin "2") (pinfunction "2_2") (pintype "passive"))
      (node (ref "R30") (pin "2") (pinfunction "2_2") (pintype "passive"))
    )
    (net (code "67") (name "Net-(Q7-E)") (class "Default")
      (node (ref "Q7") (pin "2") (pinfunction "E_2") (pintype "passive"))
      (node (ref "R31") (pin "2") (pinfunction "2_2") (pintype "passive"))
      (node (ref "R32") (pin "2") (pinfunction "2_2") (pintype "passive"))
      (node (ref "R33") (pin "2") (pinfunction "2_2") (pintype "passive"))
    )
    (net (code "68") (name "Net-(Q8-B)") (class "Default")
      (node (ref "Q8") (pin "1") (pinfunction "B_1") (pintype "passive"))
      (node (ref "R24") (pin "2") (pinfunction "2_2") (pintype "passive"))
      (node (ref "R25") (pin "2") (pinfunction "2_2") (pintype "passive"))
    )
    (net (code "69") (name "Net-(Q8-E)") (class "Default")
      (node (ref "Q8") (pin "2") (pinfunction "E_2") (pintype "passive"))
      (node (ref "R26") (pin "2") (pinfunction "2_2") (pintype "passive"))
      (node (ref "R27") (pin "2") (pinfunction "2_2") (pintype "passive"))
      (node (ref "R28") (pin "2") (pinfunction "2_2") (pintype "passive"))
    )
    (net (code "70") (name "Net-(R18-Pad2)") (class "Default")
      (node (ref "R18") (pin "2") (pinfunction "2_2") (pintype "passive"))
      (node (ref "R22") (pin "2") (pinfunction "2_2") (pintype "passive"))
    )
    (net (code "71") (name "Net-(R51-Pad2)") (class "Default")
      (node (ref "R51") (pin "2") (pinfunction "2_2") (pintype "passive"))
      (node (ref "SJ2") (pin "2") (pinfunction "2_2") (pintype "passive"))
    )
    (net (code "72") (name "Net-(T2-B)") (class "Default")
      (node (ref "C2") (pin "2") (pinfunction "2_2") (pintype "passive"))
      (node (ref "R18") (pin "1") (pinfunction "1_1") (pintype "passive"))
      (node (ref "R19") (pin "2") (pinfunction "2_2") (pintype "passive"))
      (node (ref "T2") (pin "1") (pinfunction "B_1") (pintype "passive"))
    )
    (net (code "73") (name "Net-(U$1-A0)") (class "Default")
      (node (ref "U$1") (pin "P20") (pinfunction "A0_P20") (pintype "bidirectional"))
      (node (ref "U1") (pin "P5") (pinfunction "IO_L20P_7_P5") (pintype "bidirectional"))
    )
    (net (code "74") (name "Net-(U$1-A1)") (class "Default")
      (node (ref "U$1") (pin "P19") (pinfunction "A1_P19") (pintype "bidirectional"))
      (node (ref "U1") (pin "P4") (pinfunction "IOVREF_7_P4") (pintype "bidirectional"))
    )
    (net (code "75") (name "Net-(U$1-A2)") (class "Default")
      (node (ref "U$1") (pin "P18") (pinfunction "A2_P18") (pintype "bidirectional"))
      (node (ref "U1") (pin "P2") (pinfunction "IO_L01N_7VRP_7_P2") (pintype "bidirectional"))
    )
    (net (code "76") (name "Net-(U$1-A3)") (class "Default")
      (node (ref "U$1") (pin "P17") (pinfunction "A3_P17") (pintype "bidirectional"))
      (node (ref "U1") (pin "P1") (pinfunction "IO_L01P_7VRN_7_P1") (pintype "bidirectional"))
    )
    (net (code "77") (name "Net-(U$1-A4)") (class "Default")
      (node (ref "U$1") (pin "P16") (pinfunction "A4_P16") (pintype "bidirectional"))
      (node (ref "U1") (pin "P36") (pinfunction "IO_L01N_6VRP_6_P36") (pintype "bidirectional"))
    )
    (net (code "78") (name "Net-(U$1-A5)") (class "Default")
      (node (ref "U$1") (pin "P15") (pinfunction "A5_P15") (pintype "bidirectional"))
      (node (ref "U1") (pin "P35") (pinfunction "IO_L01P_6VRN_6_P35") (pintype "bidirectional"))
    )
    (net (code "79") (name "Net-(U$1-A6)") (class "Default")
      (node (ref "U$1") (pin "P14") (pinfunction "A6_P14") (pintype "bidirectional"))
      (node (ref "U1") (pin "P33") (pinfunction "IO_L20N_6_P33") (pintype "bidirectional"))
    )
    (net (code "80") (name "Net-(U$1-A7)") (class "Default")
      (node (ref "U$1") (pin "P13") (pinfunction "A7_P13") (pintype "bidirectional"))
      (node (ref "U1") (pin "P32") (pinfunction "IO_L20P_6_P32") (pintype "bidirectional"))
    )
    (net (code "81") (name "Net-(U$1-A8)") (class "Default")
      (node (ref "U$1") (pin "P3") (pinfunction "A8_P3") (pintype "bidirectional"))
      (node (ref "U1") (pin "P21") (pinfunction "IO_L40N_6_P21") (pintype "bidirectional"))
    )
    (net (code "82") (name "Net-(U$1-A9)") (class "Default")
      (node (ref "U$1") (pin "P2") (pinfunction "A9_P2") (pintype "bidirectional"))
      (node (ref "U1") (pin "P20") (pinfunction "IO_L40P_6VREF_6_P20") (pintype "bidirectional"))
    )
    (net (code "83") (name "Net-(U$1-A10)") (class "Default")
      (node (ref "U$1") (pin "P31") (pinfunction "A10_P31") (pintype "bidirectional"))
      (node (ref "U1") (pin "P15") (pinfunction "IO_L24N_7_P15") (pintype "bidirectional"))
    )
    (net (code "84") (name "Net-(U$1-A11)") (class "Default")
      (node (ref "U$1") (pin "P1") (pinfunction "A11_P1") (pintype "bidirectional"))
      (node (ref "U1") (pin "P18") (pinfunction "IO_L40N_7VREF_7_P18") (pintype "bidirectional"))
    )
    (net (code "85") (name "Net-(U$1-A12)") (class "Default")
      (node (ref "U$1") (pin "P12") (pinfunction "A12_P12") (pintype "bidirectional"))
      (node (ref "U1") (pin "P31") (pinfunction "IO_L21N_6_P31") (pintype "bidirectional"))
    )
    (net (code "86") (name "Net-(U$1-A13)") (class "Default")
      (node (ref "U$1") (pin "P4") (pinfunction "A13_P4") (pintype "bidirectional"))
      (node (ref "U1") (pin "P23") (pinfunction "IO_L24P_6_P23") (pintype "bidirectional"))
    )
    (net (code "87") (name "Net-(U$1-A14)") (class "Default")
      (node (ref "U$1") (pin "P11") (pinfunction "A14_P11") (pintype "bidirectional"))
      (node (ref "U1") (pin "P30") (pinfunction "IO_L21P_6_P30") (pintype "bidirectional"))
    )
    (net (code "88") (name "Net-(U$1-A15)") (class "Default")
      (node (ref "U$1") (pin "P7") (pinfunction "A15_P7") (pintype "bidirectional"))
      (node (ref "U1") (pin "P26") (pinfunction "IO_L23N_6_P26") (pintype "bidirectional"))
    )
    (net (code "89") (name "Net-(U$1-A16)") (class "Default")
      (node (ref "U$1") (pin "P10") (pinfunction "A16_P10") (pintype "bidirectional"))
      (node (ref "U1") (pin "P28") (pinfunction "IO_L22N_6_P28") (pintype "bidirectional"))
    )
    (net (code "90") (name "Net-(U$1-A17)") (class "Default")
      (node (ref "U$1") (pin "P6") (pinfunction "A17_P6") (pintype "bidirectional"))
      (node (ref "U1") (pin "P25") (pinfunction "IO_L23P_6_P25") (pintype "bidirectional"))
    )
    (net (code "91") (name "Net-(U$1-A18)") (class "Default")
      (node (ref "U$1") (pin "P9") (pinfunction "A18_P9") (pintype "bidirectional"))
      (node (ref "U1") (pin "P27") (pinfunction "IO_L22P_6_P27") (pintype "bidirectional"))
    )
    (net (code "92") (name "Net-(U$1-DQ0)") (class "Default")
      (node (ref "U$1") (pin "P21") (pinfunction "DQ0_P21") (pintype "bidirectional"))
      (node (ref "U1") (pin "P6") (pinfunction "IO_L20N_7_P6") (pintype "bidirectional"))
    )
    (net (code "93") (name "Net-(U$1-DQ1)") (class "Default")
      (node (ref "U$1") (pin "P22") (pinfunction "DQ1_P22") (pintype "bidirectional"))
      (node (ref "U1") (pin "P7") (pinfunction "IO_L21P_7_P7") (pintype "bidirectional"))
    )
    (net (code "94") (name "Net-(U$1-DQ2)") (class "Default")
      (node (ref "U$1") (pin "P23") (pinfunction "DQ2_P23") (pintype "bidirectional"))
      (node (ref "U1") (pin "P8") (pinfunction "IO_L21N_7_P8") (pintype "bidirectional"))
    )
    (net (code "95") (name "Net-(U$1-DQ3)") (class "Default")
      (node (ref "U$1") (pin "P25") (pinfunction "DQ3_P25") (pintype "bidirectional"))
      (node (ref "U1") (pin "P10") (pinfunction "IO_L22P_7_P10") (pintype "bidirectional"))
    )
    (net (code "96") (name "Net-(U$1-DQ4)") (class "Default")
      (node (ref "U$1") (pin "P26") (pinfunction "DQ4_P26") (pintype "bidirectional"))
      (node (ref "U1") (pin "P11") (pinfunction "IO_L22N_7_P11") (pintype "bidirectional"))
    )
    (net (code "97") (name "Net-(U$1-DQ5)") (class "Default")
      (node (ref "U$1") (pin "P27") (pinfunction "DQ5_P27") (pintype "bidirectional"))
      (node (ref "U1") (pin "P12") (pinfunction "IO_L23P_7_P12") (pintype "bidirectional"))
    )
    (net (code "98") (name "Net-(U$1-DQ6)") (class "Default")
      (node (ref "U$1") (pin "P28") (pinfunction "DQ6_P28") (pintype "bidirectional"))
      (node (ref "U1") (pin "P13") (pinfunction "IO_L23N_7_P13") (pintype "bidirectional"))
    )
    (net (code "99") (name "Net-(U$1-DQ7)") (class "Default")
      (node (ref "U$1") (pin "P29") (pinfunction "DQ7_P29") (pintype "bidirectional"))
      (node (ref "U1") (pin "P14") (pinfunction "IO_L24P_7_P14") (pintype "bidirectional"))
    )
    (net (code "100") (name "Net-(U$1-OE)") (class "Default")
      (node (ref "U$1") (pin "P32") (pinfunction "OE_P32") (pintype "bidirectional"))
      (node (ref "U1") (pin "P17") (pinfunction "IO_L40P_7_P17") (pintype "bidirectional"))
    )
    (net (code "101") (name "Net-(U$1-WE)") (class "Default")
      (node (ref "U$1") (pin "P5") (pinfunction "WE_P5") (pintype "bidirectional"))
      (node (ref "U1") (pin "P24") (pinfunction "IO_L24N_6VREF_6_P24") (pintype "bidirectional"))
    )
    (net (code "102") (name "Net-(U1I-IO_L32P_5GCLK2)") (class "Default")
      (node (ref "U$2") (pin "OUT") (pinfunction "OUT_OUT") (pintype "output"))
      (node (ref "U1") (pin "P52") (pinfunction "IO_L32P_5GCLK2_P52") (pintype "bidirectional"))
    )
    (net (code "103") (name "Net-(U1N-TCK)") (class "Default")
      (node (ref "R2") (pin "1") (pinfunction "1_1") (pintype "passive"))
      (node (ref "U1") (pin "P110") (pinfunction "TCK_P110") (pintype "bidirectional"))
    )
    (net (code "104") (name "Net-(U1N-TDI)") (class "Default")
      (node (ref "R1") (pin "1") (pinfunction "1_1") (pintype "passive"))
      (node (ref "U1") (pin "P144") (pinfunction "TDI_P144") (pintype "bidirectional"))
    )
    (net (code "105") (name "Net-(U1N-TMS)") (class "Default")
      (node (ref "R3") (pin "1") (pinfunction "1_1") (pintype "passive"))
      (node (ref "U1") (pin "P111") (pinfunction "TMS_P111") (pintype "bidirectional"))
    )
    (net (code "106") (name "Net-(X4A-F)") (class "Default")
      (node (ref "R40") (pin "2") (pinfunction "2_2") (pintype "passive"))
      (node (ref "X4") (pin "1") (pinfunction "F_1") (pintype "passive"))
    )
    (net (code "107") (name "Net-(X4B-F)") (class "Default")
      (node (ref "R41") (pin "2") (pinfunction "2_2") (pintype "passive"))
      (node (ref "X4") (pin "2") (pinfunction "F_2") (pintype "passive"))
    )
    (net (code "108") (name "Net-(X4C-F)") (class "Default")
      (node (ref "R42") (pin "2") (pinfunction "2_2") (pintype "passive"))
      (node (ref "X4") (pin "3") (pinfunction "F_3") (pintype "passive"))
    )
    (net (code "109") (name "Net-(X4D-F)") (class "Default")
      (node (ref "R43") (pin "2") (pinfunction "2_2") (pintype "passive"))
      (node (ref "X4") (pin "4") (pinfunction "F_4") (pintype "passive"))
    )
    (net (code "110") (name "Net-(X4F-F)") (class "Default")
      (node (ref "R44") (pin "2") (pinfunction "2_2") (pintype "passive"))
      (node (ref "X4") (pin "6") (pinfunction "F_6") (pintype "passive"))
    )
    (net (code "111") (name "Net-(X4G-F)") (class "Default")
      (node (ref "R45") (pin "2") (pinfunction "2_2") (pintype "passive"))
      (node (ref "X4") (pin "7") (pinfunction "F_7") (pintype "passive"))
    )
    (net (code "112") (name "Net-(X5A-F)") (class "Default")
      (node (ref "R46") (pin "1") (pinfunction "1_1") (pintype "passive"))
      (node (ref "X5") (pin "1") (pinfunction "F_1") (pintype "passive"))
    )
    (net (code "113") (name "Net-(X5B-F)") (class "Default")
      (node (ref "R39") (pin "1") (pinfunction "1_1") (pintype "passive"))
      (node (ref "X5") (pin "2") (pinfunction "F_2") (pintype "passive"))
    )
    (net (code "114") (name "Net-(X5C-F)") (class "Default")
      (node (ref "R38") (pin "1") (pinfunction "1_1") (pintype "passive"))
      (node (ref "X5") (pin "3") (pinfunction "F_3") (pintype "passive"))
    )
    (net (code "115") (name "Net-(X5D-F)") (class "Default")
      (node (ref "R37") (pin "1") (pinfunction "1_1") (pintype "passive"))
      (node (ref "X5") (pin "4") (pinfunction "F_4") (pintype "passive"))
    )
    (net (code "116") (name "Net-(X5F-F)") (class "Default")
      (node (ref "R36") (pin "1") (pinfunction "1_1") (pintype "passive"))
      (node (ref "X5") (pin "6") (pinfunction "F_6") (pintype "passive"))
    )
    (net (code "117") (name "Net-(X5G-F)") (class "Default")
      (node (ref "R35") (pin "1") (pinfunction "1_1") (pintype "passive"))
      (node (ref "X5") (pin "7") (pinfunction "F_7") (pintype "passive"))
    )
    (net (code "118") (name "unconnected-(IC1-NC.1-Pad2)") (class "Default")
      (node (ref "IC1") (pin "2") (pinfunction "NC.1_2") (pintype "bidirectional"))
    )
    (net (code "119") (name "unconnected-(IC1-NC.2-Pad9)") (class "Default")
      (node (ref "IC1") (pin "9") (pinfunction "NC.2_9") (pintype "bidirectional"))
    )
    (net (code "120") (name "unconnected-(IC1-NC.3-Pad12)") (class "Default")
      (node (ref "IC1") (pin "12") (pinfunction "NC.3_12") (pintype "bidirectional"))
    )
    (net (code "121") (name "unconnected-(IC1-NC.4-Pad14)") (class "Default")
      (node (ref "IC1") (pin "14") (pinfunction "NC.4_14") (pintype "bidirectional"))
    )
    (net (code "122") (name "unconnected-(IC1-NC.5-Pad15)") (class "Default")
      (node (ref "IC1") (pin "15") (pinfunction "NC.5_15") (pintype "bidirectional"))
    )
    (net (code "123") (name "unconnected-(IC1-NC.6-Pad16)") (class "Default")
      (node (ref "IC1") (pin "16") (pinfunction "NC.6_16") (pintype "bidirectional"))
    )
    (net (code "124") (name "unconnected-(IC1-{slash}CEO-Pad13)") (class "Default")
      (node (ref "IC1") (pin "13") (pinfunction "/CEO_13") (pintype "bidirectional"))
    )
    (net (code "125") (name "unconnected-(REG1.2-VOUT2-Pad2)") (class "Default")
      (node (ref "REG1.2") (pin "2") (pinfunction "VOUT2_2") (pintype "bidirectional"))
    )
    (net (code "126") (name "unconnected-(U$2-TRI-PadENA)") (class "Default")
      (node (ref "U$2") (pin "ENA") (pinfunction "TRI_ENA") (pintype "input"))
    )
    (net (code "127") (name "unconnected-(U$3-AREF-Pad42)") (class "Default")
      (node (ref "U$3") (pin "42") (pinfunction "AREF_42") (pintype "bidirectional"))
    )
    (net (code "128") (name "unconnected-(U$3-AVCC-Pad24)") (class "Default")
      (node (ref "U$3") (pin "24") (pinfunction "AVCC_24") (pintype "bidirectional"))
    )
    (net (code "129") (name "unconnected-(U$3-AVCC1-Pad44)") (class "Default")
      (node (ref "U$3") (pin "44") (pinfunction "AVCC1_44") (pintype "bidirectional"))
    )
    (net (code "130") (name "unconnected-(U$3-D+-Pad4)") (class "Default")
      (node (ref "U$3") (pin "4") (pinfunction "D+_4") (pintype "bidirectional"))
    )
    (net (code "131") (name "unconnected-(U$3-D--Pad3)") (class "Default")
      (node (ref "U$3") (pin "3") (pinfunction "D-_3") (pintype "bidirectional"))
    )
    (net (code "132") (name "unconnected-(U$3-GND-Pad15)") (class "Default")
      (node (ref "U$3") (pin "15") (pinfunction "GND_15") (pintype "bidirectional"))
    )
    (net (code "133") (name "unconnected-(U$3-GND1-Pad23)") (class "Default")
      (node (ref "U$3") (pin "23") (pinfunction "GND1_23") (pintype "bidirectional"))
    )
    (net (code "134") (name "unconnected-(U$3-GND2-Pad35)") (class "Default")
      (node (ref "U$3") (pin "35") (pinfunction "GND2_35") (pintype "bidirectional"))
    )
    (net (code "135") (name "unconnected-(U$3-GND3-Pad43)") (class "Default")
      (node (ref "U$3") (pin "43") (pinfunction "GND3_43") (pintype "bidirectional"))
    )
    (net (code "136") (name "unconnected-(U$3-PB4(ADC11)-Pad28)") (class "Default")
      (node (ref "U$3") (pin "28") (pinfunction "PB4(ADC11)_28") (pintype "bidirectional"))
    )
    (net (code "137") (name "unconnected-(U$3-PB5(OC1A{slash}ADC12{slash}~{OC4B})-Pad29)") (class "Default")
      (node (ref "U$3") (pin "29") (pinfunction "PB5(OC1A/ADC12/~{OC4B})_29") (pintype "bidirectional"))
    )
    (net (code "138") (name "unconnected-(U$3-PB6(OC1B{slash}OC4B{slash}ADC13)-Pad30)") (class "Default")
      (node (ref "U$3") (pin "30") (pinfunction "PB6(OC1B/OC4B/ADC13)_30") (pintype "bidirectional"))
    )
    (net (code "139") (name "unconnected-(U$3-PB7(OC0A{slash}OC1C{slash}RTS)-Pad12)") (class "Default")
      (node (ref "U$3") (pin "12") (pinfunction "PB7(OC0A/OC1C/RTS)_12") (pintype "bidirectional"))
    )
    (net (code "140") (name "unconnected-(U$3-PC6(OC3A{slash}~{OC4A})-Pad31)") (class "Default")
      (node (ref "U$3") (pin "31") (pinfunction "PC6(OC3A/~{OC4A})_31") (pintype "bidirectional"))
    )
    (net (code "141") (name "unconnected-(U$3-PC7(ICP3{slash}CLK0{slash}OC4A)-Pad32)") (class "Default")
      (node (ref "U$3") (pin "32") (pinfunction "PC7(ICP3/CLK0/OC4A)_32") (pintype "bidirectional"))
    )
    (net (code "142") (name "unconnected-(U$3-PD0(INT0{slash}OC0B{slash}SCL)-Pad18)") (class "Default")
      (node (ref "U$3") (pin "18") (pinfunction "PD0(INT0/OC0B/SCL)_18") (pintype "bidirectional"))
    )
    (net (code "143") (name "unconnected-(U$3-PD1(INT1{slash}SDA)-Pad19)") (class "Default")
      (node (ref "U$3") (pin "19") (pinfunction "PD1(INT1/SDA)_19") (pintype "bidirectional"))
    )
    (net (code "144") (name "unconnected-(U$3-PD2(INT2{slash}RXD1)-Pad20)") (class "Default")
      (node (ref "U$3") (pin "20") (pinfunction "PD2(INT2/RXD1)_20") (pintype "bidirectional"))
    )
    (net (code "145") (name "unconnected-(U$3-PD3(INT3{slash}TXD1)-Pad21)") (class "Default")
      (node (ref "U$3") (pin "21") (pinfunction "PD3(INT3/TXD1)_21") (pintype "bidirectional"))
    )
    (net (code "146") (name "unconnected-(U$3-PD4(ICP1{slash}ADC8)-Pad25)") (class "Default")
      (node (ref "U$3") (pin "25") (pinfunction "PD4(ICP1/ADC8)_25") (pintype "bidirectional"))
    )
    (net (code "147") (name "unconnected-(U$3-PD5(XCK{slash}CTS)-Pad22)") (class "Default")
      (node (ref "U$3") (pin "22") (pinfunction "PD5(XCK/CTS)_22") (pintype "bidirectional"))
    )
    (net (code "148") (name "unconnected-(U$3-PD6(T1{slash}ADC9{slash}~{OC4D})-Pad26)") (class "Default")
      (node (ref "U$3") (pin "26") (pinfunction "PD6(T1/ADC9/~{OC4D})_26") (pintype "bidirectional"))
    )
    (net (code "149") (name "unconnected-(U$3-PD7(OC4D{slash}ADC10{slash}T0)-Pad27)") (class "Default")
      (node (ref "U$3") (pin "27") (pinfunction "PD7(OC4D/ADC10/T0)_27") (pintype "bidirectional"))
    )
    (net (code "150") (name "unconnected-(U$3-PE2(~{HWB})-Pad33)") (class "Default")
      (node (ref "U$3") (pin "33") (pinfunction "PE2(~{HWB})_33") (pintype "bidirectional"))
    )
    (net (code "151") (name "unconnected-(U$3-PE6(INT.6{slash}AIN0)-Pad1)") (class "Default")
      (node (ref "U$3") (pin "1") (pinfunction "PE6(INT.6/AIN0)_1") (pintype "bidirectional"))
    )
    (net (code "152") (name "unconnected-(U$3-PF0(ADC0)-Pad41)") (class "Default")
      (node (ref "U$3") (pin "41") (pinfunction "PF0(ADC0)_41") (pintype "bidirectional"))
    )
    (net (code "153") (name "unconnected-(U$3-PF1(ADC1)-Pad40)") (class "Default")
      (node (ref "U$3") (pin "40") (pinfunction "PF1(ADC1)_40") (pintype "bidirectional"))
    )
    (net (code "154") (name "unconnected-(U$3-UCAP-Pad6)") (class "Default")
      (node (ref "U$3") (pin "6") (pinfunction "UCAP_6") (pintype "bidirectional"))
    )
    (net (code "155") (name "unconnected-(U$3-UGND-Pad5)") (class "Default")
      (node (ref "U$3") (pin "5") (pinfunction "UGND_5") (pintype "bidirectional"))
    )
    (net (code "156") (name "unconnected-(U$3-UVCC-Pad2)") (class "Default")
      (node (ref "U$3") (pin "2") (pinfunction "UVCC_2") (pintype "bidirectional"))
    )
    (net (code "157") (name "unconnected-(U$3-VBUS-Pad7)") (class "Default")
      (node (ref "U$3") (pin "7") (pinfunction "VBUS_7") (pintype "bidirectional"))
    )
    (net (code "158") (name "unconnected-(U$3-VCC-Pad14)") (class "Default")
      (node (ref "U$3") (pin "14") (pinfunction "VCC_14") (pintype "bidirectional"))
    )
    (net (code "159") (name "unconnected-(U$3-VCC1-Pad34)") (class "Default")
      (node (ref "U$3") (pin "34") (pinfunction "VCC1_34") (pintype "bidirectional"))
    )
    (net (code "160") (name "unconnected-(U$3-XTAL1-Pad17)") (class "Default")
      (node (ref "U$3") (pin "17") (pinfunction "XTAL1_17") (pintype "bidirectional"))
    )
    (net (code "161") (name "unconnected-(U$3-XTAL2-Pad16)") (class "Default")
      (node (ref "U$3") (pin "16") (pinfunction "XTAL2_16") (pintype "bidirectional"))
    )
    (net (code "162") (name "unconnected-(U$3-{slash}RESET-Pad13)") (class "Default")
      (node (ref "U$3") (pin "13") (pinfunction "/RESET_13") (pintype "bidirectional"))
    )
    (net (code "163") (name "unconnected-(U1A-IO_L27P_0-PadP135)") (class "Default")
      (node (ref "U1") (pin "P135") (pinfunction "IO_L27P_0_P135") (pintype "bidirectional"))
    )
    (net (code "164") (name "unconnected-(U1A-IO_L30N_0-PadP132)") (class "Default")
      (node (ref "U1") (pin "P132") (pinfunction "IO_L30N_0_P132") (pintype "bidirectional"))
    )
    (net (code "165") (name "unconnected-(U1A-IO_L30P_0-PadP131)") (class "Default")
      (node (ref "U1") (pin "P131") (pinfunction "IO_L30P_0_P131") (pintype "bidirectional"))
    )
    (net (code "166") (name "unconnected-(U1A-IO_L31N_0-PadP130)") (class "Default")
      (node (ref "U1") (pin "P130") (pinfunction "IO_L31N_0_P130") (pintype "bidirectional"))
    )
    (net (code "167") (name "unconnected-(U1A-IO_L31P_0VREF_0-PadP129)") (class "Default")
      (node (ref "U1") (pin "P129") (pinfunction "IO_L31P_0VREF_0_P129") (pintype "bidirectional"))
    )
    (net (code "168") (name "unconnected-(U1A-IO_L32N_0GCLK7-PadP128)") (class "Default")
      (node (ref "U1") (pin "P128") (pinfunction "IO_L32N_0GCLK7_P128") (pintype "bidirectional"))
    )
    (net (code "169") (name "unconnected-(U1A-IO_L32P_0GCLK6-PadP127)") (class "Default")
      (node (ref "U1") (pin "P127") (pinfunction "IO_L32P_0GCLK6_P127") (pintype "bidirectional"))
    )
    (net (code "170") (name "unconnected-(U1C-IO-PadP116)") (class "Default")
      (node (ref "U1") (pin "P116") (pinfunction "IO_P116") (pintype "bidirectional"))
    )
    (net (code "171") (name "unconnected-(U1C-IO_L01N_1VRP_1-PadP113)") (class "Default")
      (node (ref "U1") (pin "P113") (pinfunction "IO_L01N_1VRP_1_P113") (pintype "bidirectional"))
    )
    (net (code "172") (name "unconnected-(U1C-IO_L01P_1VRN_1-PadP112)") (class "Default")
      (node (ref "U1") (pin "P112") (pinfunction "IO_L01P_1VRN_1_P112") (pintype "bidirectional"))
    )
    (net (code "173") (name "unconnected-(U1C-IO_L28N_1-PadP119)") (class "Default")
      (node (ref "U1") (pin "P119") (pinfunction "IO_L28N_1_P119") (pintype "bidirectional"))
    )
    (net (code "174") (name "unconnected-(U1C-IO_L28P_1-PadP118)") (class "Default")
      (node (ref "U1") (pin "P118") (pinfunction "IO_L28P_1_P118") (pintype "bidirectional"))
    )
    (net (code "175") (name "unconnected-(U1C-IO_L31N_1VREF_1-PadP123)") (class "Default")
      (node (ref "U1") (pin "P123") (pinfunction "IO_L31N_1VREF_1_P123") (pintype "bidirectional"))
    )
    (net (code "176") (name "unconnected-(U1C-IO_L31P_1-PadP122)") (class "Default")
      (node (ref "U1") (pin "P122") (pinfunction "IO_L31P_1_P122") (pintype "bidirectional"))
    )
    (net (code "177") (name "unconnected-(U1C-IO_L32N_1GCLK5-PadP125)") (class "Default")
      (node (ref "U1") (pin "P125") (pinfunction "IO_L32N_1GCLK5_P125") (pintype "bidirectional"))
    )
    (net (code "178") (name "unconnected-(U1C-IO_L32P_1GCLK4-PadP124)") (class "Default")
      (node (ref "U1") (pin "P124") (pinfunction "IO_L32P_1GCLK4_P124") (pintype "bidirectional"))
    )
    (net (code "179") (name "unconnected-(U1D-IO_L01N_2VRP_2-PadP108)") (class "Default")
      (node (ref "U1") (pin "P108") (pinfunction "IO_L01N_2VRP_2_P108") (pintype "bidirectional"))
    )
    (net (code "180") (name "unconnected-(U1D-IO_L01P_2VRN_2-PadP107)") (class "Default")
      (node (ref "U1") (pin "P107") (pinfunction "IO_L01P_2VRN_2_P107") (pintype "bidirectional"))
    )
    (net (code "181") (name "unconnected-(U1D-IO_L20N_2-PadP105)") (class "Default")
      (node (ref "U1") (pin "P105") (pinfunction "IO_L20N_2_P105") (pintype "bidirectional"))
    )
    (net (code "182") (name "unconnected-(U1D-IO_L20P_2-PadP104)") (class "Default")
      (node (ref "U1") (pin "P104") (pinfunction "IO_L20P_2_P104") (pintype "bidirectional"))
    )
    (net (code "183") (name "unconnected-(U1D-IO_L21N_2-PadP103)") (class "Default")
      (node (ref "U1") (pin "P103") (pinfunction "IO_L21N_2_P103") (pintype "bidirectional"))
    )
    (net (code "184") (name "unconnected-(U1D-IO_L21P_2-PadP102)") (class "Default")
      (node (ref "U1") (pin "P102") (pinfunction "IO_L21P_2_P102") (pintype "bidirectional"))
    )
    (net (code "185") (name "unconnected-(U1D-IO_L22N_2-PadP100)") (class "Default")
      (node (ref "U1") (pin "P100") (pinfunction "IO_L22N_2_P100") (pintype "bidirectional"))
    )
    (net (code "186") (name "unconnected-(U1D-IO_L22P_2-PadP99)") (class "Default")
      (node (ref "U1") (pin "P99") (pinfunction "IO_L22P_2_P99") (pintype "bidirectional"))
    )
    (net (code "187") (name "unconnected-(U1D-IO_L23N_2VREF_2-PadP98)") (class "Default")
      (node (ref "U1") (pin "P98") (pinfunction "IO_L23N_2VREF_2_P98") (pintype "bidirectional"))
    )
    (net (code "188") (name "unconnected-(U1D-IO_L23P_2-PadP97)") (class "Default")
      (node (ref "U1") (pin "P97") (pinfunction "IO_L23P_2_P97") (pintype "bidirectional"))
    )
    (net (code "189") (name "unconnected-(U1D-IO_L24N_2-PadP96)") (class "Default")
      (node (ref "U1") (pin "P96") (pinfunction "IO_L24N_2_P96") (pintype "bidirectional"))
    )
    (net (code "190") (name "unconnected-(U1D-IO_L24P_2-PadP95)") (class "Default")
      (node (ref "U1") (pin "P95") (pinfunction "IO_L24P_2_P95") (pintype "bidirectional"))
    )
    (net (code "191") (name "unconnected-(U1D-IO_L40N_2-PadP93)") (class "Default")
      (node (ref "U1") (pin "P93") (pinfunction "IO_L40N_2_P93") (pintype "bidirectional"))
    )
    (net (code "192") (name "unconnected-(U1D-IO_L40P_2VREF_2-PadP92)") (class "Default")
      (node (ref "U1") (pin "P92") (pinfunction "IO_L40P_2VREF_2_P92") (pintype "bidirectional"))
    )
    (net (code "193") (name "unconnected-(U1F-IO-PadP76)") (class "Default")
      (node (ref "U1") (pin "P76") (pinfunction "IO_P76") (pintype "bidirectional"))
    )
    (net (code "194") (name "unconnected-(U1F-IO_L01N_3VRP_3-PadP74)") (class "Default")
      (node (ref "U1") (pin "P74") (pinfunction "IO_L01N_3VRP_3_P74") (pintype "bidirectional"))
    )
    (net (code "195") (name "unconnected-(U1F-IO_L01P_3VRN_3-PadP73)") (class "Default")
      (node (ref "U1") (pin "P73") (pinfunction "IO_L01P_3VRN_3_P73") (pintype "bidirectional"))
    )
    (net (code "196") (name "unconnected-(U1F-IO_L20N_3-PadP78)") (class "Default")
      (node (ref "U1") (pin "P78") (pinfunction "IO_L20N_3_P78") (pintype "bidirectional"))
    )
    (net (code "197") (name "unconnected-(U1F-IO_L20P_3-PadP77)") (class "Default")
      (node (ref "U1") (pin "P77") (pinfunction "IO_L20P_3_P77") (pintype "bidirectional"))
    )
    (net (code "198") (name "unconnected-(U1F-IO_L21N_3-PadP80)") (class "Default")
      (node (ref "U1") (pin "P80") (pinfunction "IO_L21N_3_P80") (pintype "bidirectional"))
    )
    (net (code "199") (name "unconnected-(U1F-IO_L21P_3-PadP79)") (class "Default")
      (node (ref "U1") (pin "P79") (pinfunction "IO_L21P_3_P79") (pintype "bidirectional"))
    )
    (net (code "200") (name "unconnected-(U1F-IO_L22N_3-PadP83)") (class "Default")
      (node (ref "U1") (pin "P83") (pinfunction "IO_L22N_3_P83") (pintype "bidirectional"))
    )
    (net (code "201") (name "unconnected-(U1F-IO_L22P_3-PadP82)") (class "Default")
      (node (ref "U1") (pin "P82") (pinfunction "IO_L22P_3_P82") (pintype "bidirectional"))
    )
    (net (code "202") (name "unconnected-(U1F-IO_L23N_3-PadP85)") (class "Default")
      (node (ref "U1") (pin "P85") (pinfunction "IO_L23N_3_P85") (pintype "bidirectional"))
    )
    (net (code "203") (name "unconnected-(U1F-IO_L23P_3VREF_3-PadP84)") (class "Default")
      (node (ref "U1") (pin "P84") (pinfunction "IO_L23P_3VREF_3_P84") (pintype "bidirectional"))
    )
    (net (code "204") (name "unconnected-(U1F-IO_L24N_3-PadP87)") (class "Default")
      (node (ref "U1") (pin "P87") (pinfunction "IO_L24N_3_P87") (pintype "bidirectional"))
    )
    (net (code "205") (name "unconnected-(U1F-IO_L24P_3-PadP86)") (class "Default")
      (node (ref "U1") (pin "P86") (pinfunction "IO_L24P_3_P86") (pintype "bidirectional"))
    )
    (net (code "206") (name "unconnected-(U1F-IO_L40N_3VREF_3-PadP90)") (class "Default")
      (node (ref "U1") (pin "P90") (pinfunction "IO_L40N_3VREF_3_P90") (pintype "bidirectional"))
    )
    (net (code "207") (name "unconnected-(U1F-IO_L40P_3-PadP89)") (class "Default")
      (node (ref "U1") (pin "P89") (pinfunction "IO_L40P_3_P89") (pintype "bidirectional"))
    )
    (net (code "208") (name "unconnected-(U1G-IOVREF_4-PadP70)") (class "Default")
      (node (ref "U1") (pin "P70") (pinfunction "IOVREF_4_P70") (pintype "bidirectional"))
    )
    (net (code "209") (name "unconnected-(U1G-IO_L01N_4VRP_4-PadP69)") (class "Default")
      (node (ref "U1") (pin "P69") (pinfunction "IO_L01N_4VRP_4_P69") (pintype "bidirectional"))
    )
    (net (code "210") (name "unconnected-(U1G-IO_L01P_4VRN_4-PadP68)") (class "Default")
      (node (ref "U1") (pin "P68") (pinfunction "IO_L01P_4VRN_4_P68") (pintype "bidirectional"))
    )
    (net (code "211") (name "unconnected-(U1G-IO_L27P_4D1-PadP63)") (class "Default")
      (node (ref "U1") (pin "P63") (pinfunction "IO_L27P_4D1_P63") (pintype "bidirectional"))
    )
    (net (code "212") (name "unconnected-(U1G-IO_L30N_4D2-PadP60)") (class "Default")
      (node (ref "U1") (pin "P60") (pinfunction "IO_L30N_4D2_P60") (pintype "bidirectional"))
    )
    (net (code "213") (name "unconnected-(U1G-IO_L30P_4D3-PadP59)") (class "Default")
      (node (ref "U1") (pin "P59") (pinfunction "IO_L30P_4D3_P59") (pintype "bidirectional"))
    )
    (net (code "214") (name "unconnected-(U1G-IO_L31P_4DOUTBUSY-PadP57)") (class "Default")
      (node (ref "U1") (pin "P57") (pinfunction "IO_L31P_4DOUTBUSY_P57") (pintype "bidirectional"))
    )
    (net (code "215") (name "unconnected-(U1G-IO_L32N_4GCLK1-PadP56)") (class "Default")
      (node (ref "U1") (pin "P56") (pinfunction "IO_L32N_4GCLK1_P56") (pintype "bidirectional"))
    )
    (net (code "216") (name "unconnected-(U1G-IO_L32P_4GCLK0-PadP55)") (class "Default")
      (node (ref "U1") (pin "P55") (pinfunction "IO_L32P_4GCLK0_P55") (pintype "bidirectional"))
    )
    (net (code "217") (name "unconnected-(U1I-IO_L32N_5GCLK3-PadP53)") (class "Default")
      (node (ref "U1") (pin "P53") (pinfunction "IO_L32N_5GCLK3_P53") (pintype "bidirectional"))
    )
    (net (code "218") (name "unconnected-(U1N-HSWAP_EN-PadP142)") (class "Default")
      (node (ref "U1") (pin "P142") (pinfunction "HSWAP_EN_P142") (pintype "bidirectional"))
    )
    (net (code "219") (name "unconnected-(X1-3-Pad2)") (class "Default")
      (node (ref "X1") (pin "2") (pinfunction "3_2") (pintype "passive"))
    )
    (net (code "220") (name "unconnected-(X2-Pad10)") (class "Default")
      (node (ref "X2") (pin "10") (pinfunction "10_10") (pintype "passive"))
    )
    (net (code "221") (name "unconnected-(X2-Pad12)") (class "Default")
      (node (ref "X2") (pin "12") (pinfunction "12_12") (pintype "passive"))
    )
    (net (code "222") (name "unconnected-(X3-Pad2)") (class "Default")
      (node (ref "X3") (pin "2") (pinfunction "2_2") (pintype "passive"))
    )
    (net (code "223") (name "unconnected-(X3-Pad8)") (class "Default")
      (node (ref "X3") (pin "8") (pinfunction "8_8") (pintype "passive"))
    )
    (net (code "224") (name "unconnected-(X4-PadG2)") (class "Default")
      (node (ref "X4") (pin "G2") (pinfunction "G2_G2") (pintype "passive"))
    )
    (net (code "225") (name "unconnected-(X5-PadG2)") (class "Default")
      (node (ref "X5") (pin "G2") (pinfunction "G2_G2") (pintype "passive"))
    )
  )
)
